# ATTiny-A4950.net
KiCad netlist of a schematic drawn in EAGLE
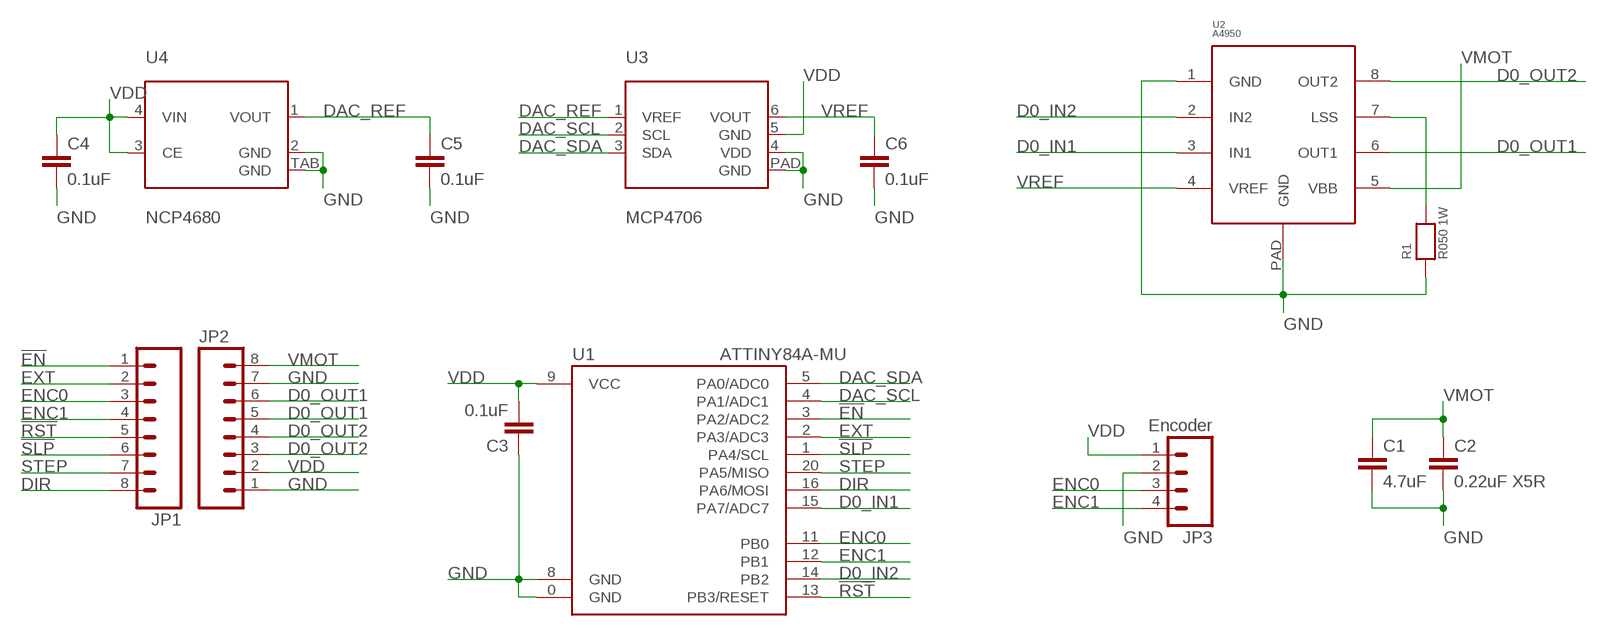
[diagram p0: schematic, sheet 1]

(export (version "E")
  (design (tool "Eeschema 10.0.6"))
  (components
    (comp (ref "C1")
      (value "4.7uF")
      (footprint "eagle-import:1206")
      (libsource (lib "eagle-import") (part "CAP1206"))
    )
    (comp (ref "C2")
      (value "0.22uF X5R")
      (footprint "eagle-import:0402-CAP")
      (libsource (lib "eagle-import") (part "CAP0402-CAP"))
    )
    (comp (ref "C3")
      (value "0.1uF")
      (footprint "eagle-import:0402-CAP")
      (libsource (lib "eagle-import") (part "CAP0402-CAP"))
    )
    (comp (ref "C4")
      (value "0.1uF")
      (footprint "eagle-import:0402-CAP")
      (libsource (lib "eagle-import") (part "CAP0402-CAP"))
    )
    (comp (ref "C5")
      (value "0.1uF")
      (footprint "eagle-import:0402-CAP")
      (libsource (lib "eagle-import") (part "CAP0402-CAP"))
    )
    (comp (ref "C6")
      (value "0.1uF")
      (footprint "eagle-import:0402-CAP")
      (libsource (lib "eagle-import") (part "CAP0402-CAP"))
    )
    (comp (ref "JP1")
      (value "M081X08")
      (footprint "eagle-import:1X08")
      (libsource (lib "eagle-import") (part "M081X08"))
    )
    (comp (ref "JP2")
      (value "M081X08")
      (footprint "eagle-import:1X08")
      (libsource (lib "eagle-import") (part "M081X08"))
    )
    (comp (ref "JP3")
      (value "Encoder")
      (footprint "eagle-import:1X04")
      (libsource (lib "eagle-import") (part "M04PTH"))
    )
    (comp (ref "R1")
      (value "R050 1W")
      (footprint "eagle-import:1206")
      (libsource (lib "eagle-import") (part "RESISTOR1206"))
    )
    (comp (ref "U1")
      (value "ATTINY84A-MU")
      (footprint "eagle-import:QFN20")
      (libsource (lib "eagle-import") (part "ATTINY24QFN"))
    )
    (comp (ref "U2")
      (value "A4950")
      (footprint "eagle-import:SOICN8-PAD")
      (libsource (lib "eagle-import") (part "A4950"))
    )
    (comp (ref "U3")
      (value "MCP4706")
      (footprint "eagle-import:6DFN")
      (libsource (lib "eagle-import") (part "MCP47X6"))
    )
    (comp (ref "U4")
      (value "NCP4680")
      (footprint "eagle-import:XDFN4")
      (libsource (lib "eagle-import") (part "NCP4680"))
    )
  )
  (nets
    (net (code "1") (name "/D0_IN1") (class "Default")
      (node (ref "U1") (pin "15") (pinfunction "PA7/ADC7_15") (pintype "bidirectional"))
      (node (ref "U2") (pin "3") (pinfunction "IN1_3") (pintype "bidirectional"))
    )
    (net (code "2") (name "/D0_IN2") (class "Default")
      (node (ref "U1") (pin "14") (pinfunction "PB2_14") (pintype "bidirectional"))
      (node (ref "U2") (pin "2") (pinfunction "IN2_2") (pintype "bidirectional"))
    )
    (net (code "3") (name "/D0_OUT1") (class "Default")
      (node (ref "JP2") (pin "5") (pinfunction "5_5") (pintype "passive"))
      (node (ref "JP2") (pin "6") (pinfunction "6_6") (pintype "passive"))
      (node (ref "U2") (pin "6") (pinfunction "OUT1_6") (pintype "bidirectional"))
    )
    (net (code "4") (name "/D0_OUT2") (class "Default")
      (node (ref "JP2") (pin "3") (pinfunction "3_3") (pintype "passive"))
      (node (ref "JP2") (pin "4") (pinfunction "4_4") (pintype "passive"))
      (node (ref "U2") (pin "8") (pinfunction "OUT2_8") (pintype "bidirectional"))
    )
    (net (code "5") (name "/DAC_REF") (class "Default")
      (node (ref "C5") (pin "1") (pinfunction "1_1") (pintype "passive"))
      (node (ref "U3") (pin "1") (pinfunction "VREF_1") (pintype "bidirectional"))
      (node (ref "U4") (pin "1") (pinfunction "VOUT_1") (pintype "bidirectional"))
    )
    (net (code "6") (name "/DAC_SCL") (class "Default")
      (node (ref "U1") (pin "4") (pinfunction "PA1/ADC1_4") (pintype "bidirectional"))
      (node (ref "U3") (pin "2") (pinfunction "SCL_2") (pintype "bidirectional"))
    )
    (net (code "7") (name "/DAC_SDA") (class "Default")
      (node (ref "U1") (pin "5") (pinfunction "PA0/ADC0_5") (pintype "bidirectional"))
      (node (ref "U3") (pin "3") (pinfunction "SDA_3") (pintype "bidirectional"))
    )
    (net (code "8") (name "/DIR") (class "Default")
      (node (ref "JP1") (pin "8") (pinfunction "8_8") (pintype "passive"))
      (node (ref "U1") (pin "16") (pinfunction "PA6/MOSI_16") (pintype "bidirectional"))
    )
    (net (code "9") (name "/ENC0") (class "Default")
      (node (ref "JP1") (pin "3") (pinfunction "3_3") (pintype "passive"))
      (node (ref "JP3") (pin "3") (pinfunction "3_3") (pintype "passive"))
      (node (ref "U1") (pin "11") (pinfunction "PB0_11") (pintype "bidirectional"))
    )
    (net (code "10") (name "/ENC1") (class "Default")
      (node (ref "JP1") (pin "4") (pinfunction "4_4") (pintype "passive"))
      (node (ref "JP3") (pin "4") (pinfunction "4_4") (pintype "passive"))
      (node (ref "U1") (pin "12") (pinfunction "PB1_12") (pintype "bidirectional"))
    )
    (net (code "11") (name "/EXT") (class "Default")
      (node (ref "JP1") (pin "2") (pinfunction "2_2") (pintype "passive"))
      (node (ref "U1") (pin "2") (pinfunction "PA3/ADC3_2") (pintype "bidirectional"))
    )
    (net (code "12") (name "/GND") (class "Default")
      (node (ref "C1") (pin "2") (pinfunction "2_2") (pintype "passive"))
      (node (ref "C2") (pin "2") (pinfunction "2_2") (pintype "passive"))
      (node (ref "C3") (pin "1") (pinfunction "1_1") (pintype "passive"))
      (node (ref "C4") (pin "2") (pinfunction "2_2") (pintype "passive"))
      (node (ref "C5") (pin "2") (pinfunction "2_2") (pintype "passive"))
      (node (ref "C6") (pin "2") (pinfunction "2_2") (pintype "passive"))
      (node (ref "JP2") (pin "1") (pinfunction "1_1") (pintype "passive"))
      (node (ref "JP2") (pin "7") (pinfunction "7_7") (pintype "passive"))
      (node (ref "JP3") (pin "2") (pinfunction "2_2") (pintype "passive"))
      (node (ref "R1") (pin "1") (pinfunction "1_1") (pintype "passive"))
      (node (ref "U1") (pin "0") (pinfunction "GND_0") (pintype "bidirectional"))
      (node (ref "U1") (pin "8") (pinfunction "GND_8") (pintype "bidirectional"))
      (node (ref "U2") (pin "1") (pinfunction "GND_1") (pintype "bidirectional"))
      (node (ref "U2") (pin "PAD") (pinfunction "GND_PAD") (pintype "bidirectional"))
      (node (ref "U3") (pin "4") (pinfunction "VDD_4") (pintype "bidirectional"))
      (node (ref "U3") (pin "PAD") (pinfunction "GND_PAD") (pintype "bidirectional"))
      (node (ref "U4") (pin "2") (pinfunction "GND_2") (pintype "bidirectional"))
      (node (ref "U4") (pin "TAB") (pinfunction "GND_TAB") (pintype "bidirectional"))
    )
    (net (code "13") (name "/STEP") (class "Default")
      (node (ref "JP1") (pin "7") (pinfunction "7_7") (pintype "passive"))
      (node (ref "U1") (pin "20") (pinfunction "PA5/MISO_20") (pintype "bidirectional"))
    )
    (net (code "14") (name "/VDD") (class "Default")
      (node (ref "C3") (pin "2") (pinfunction "2_2") (pintype "passive"))
      (node (ref "C4") (pin "1") (pinfunction "1_1") (pintype "passive"))
      (node (ref "JP2") (pin "2") (pinfunction "2_2") (pintype "passive"))
      (node (ref "JP3") (pin "1") (pinfunction "1_1") (pintype "passive"))
      (node (ref "U1") (pin "9") (pinfunction "VCC_9") (pintype "bidirectional"))
      (node (ref "U3") (pin "5") (pinfunction "GND_5") (pintype "bidirectional"))
      (node (ref "U4") (pin "3") (pinfunction "CE_3") (pintype "bidirectional"))
      (node (ref "U4") (pin "4") (pinfunction "VIN_4") (pintype "bidirectional"))
    )
    (net (code "15") (name "/VMOT") (class "Default")
      (node (ref "C1") (pin "1") (pinfunction "1_1") (pintype "passive"))
      (node (ref "C2") (pin "1") (pinfunction "1_1") (pintype "passive"))
      (node (ref "JP2") (pin "8") (pinfunction "8_8") (pintype "passive"))
      (node (ref "U2") (pin "5") (pinfunction "VBB_5") (pintype "bidirectional"))
    )
    (net (code "16") (name "/VREF") (class "Default")
      (node (ref "C6") (pin "1") (pinfunction "1_1") (pintype "passive"))
      (node (ref "U2") (pin "4") (pinfunction "VREF_4") (pintype "bidirectional"))
      (node (ref "U3") (pin "6") (pinfunction "VOUT_6") (pintype "bidirectional"))
    )
    (net (code "17") (name "/~{EN}") (class "Default")
      (node (ref "JP1") (pin "1") (pinfunction "1_1") (pintype "passive"))
      (node (ref "U1") (pin "3") (pinfunction "PA2/ADC2_3") (pintype "bidirectional"))
    )
    (net (code "18") (name "/~{RST}") (class "Default")
      (node (ref "JP1") (pin "5") (pinfunction "5_5") (pintype "passive"))
      (node (ref "U1") (pin "13") (pinfunction "PB3/RESET_13") (pintype "bidirectional"))
    )
    (net (code "19") (name "/~{SLP}") (class "Default")
      (node (ref "JP1") (pin "6") (pinfunction "6_6") (pintype "passive"))
      (node (ref "U1") (pin "1") (pinfunction "PA4/SCL_1") (pintype "bidirectional"))
    )
    (net (code "20") (name "Net-(U2-LSS)") (class "Default")
      (node (ref "R1") (pin "2") (pinfunction "2_2") (pintype "passive"))
      (node (ref "U2") (pin "7") (pinfunction "LSS_7") (pintype "bidirectional"))
    )
  )
)
